# 04-Accel.net
KiCad netlist of a schematic drawn in Altium Designer
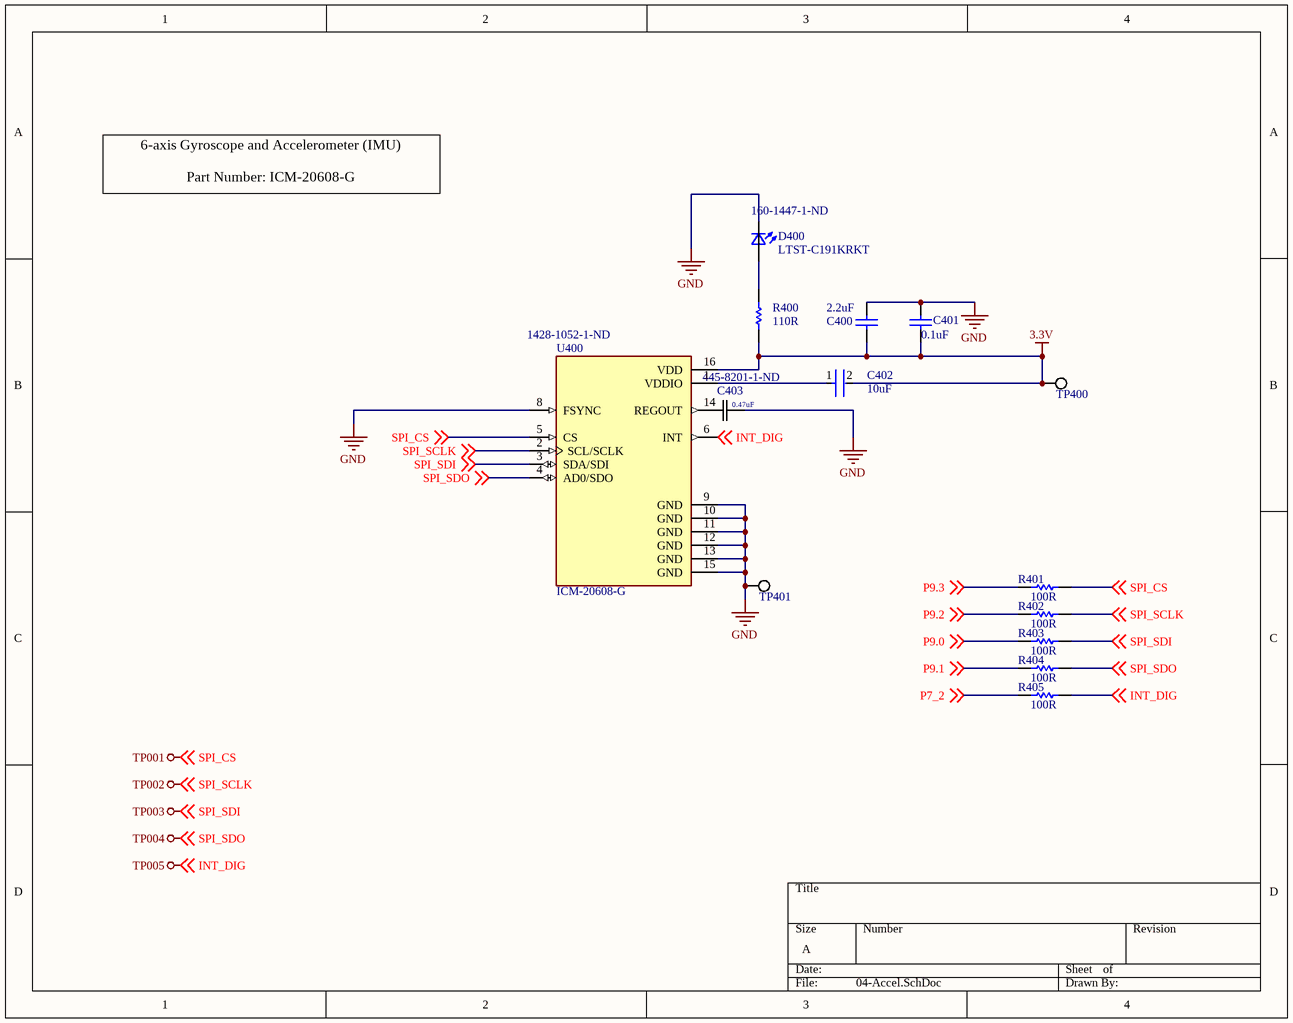
[diagram p0: 04-Accel.SchDoc]

(export (version "E")
  (design (tool "Eeschema 10.0.6"))
  (components
    (comp (ref "C400")
      (value "2.2uF")
      (footprint "CAPC2013X145X50ML20T25")
      (fields (field (name "PART NUMBER") "C0805C225K9PACTU") (field (name "MANUFACTURER") "Kemet"))
      (libsource (lib "Altium Content Vault") (part "CAP"))
    )
    (comp (ref "C401")
      (value "0.1uF")
      (footprint "CAPC2013X145X50LL20T25")
      (fields (field (name "MANUFACTURER") "Kemet") (field (name "PART NUMBER") "C0805C104K9RACTU"))
      (libsource (lib "Altium Content Vault") (part "CAP"))
    )
    (comp (ref "C402")
      (value "10uF")
      (footprint "FP-C0805C-DN-MFG")
      (description "CAP CER 10000PF 10V X7R 0805")
      (fields
        (field (name "MANUFACTURER PART NUMBER") "C0805C103K8RACTU")
        (field (name "OCTOPART") "https://octopart.com/c0805c103k8ractu-kemet-12595572")
      )
      (libsource (lib "Altium Content Vault") (part "b4654b650e69147ec39a6b967a45e02"))
    )
    (comp (ref "C403")
      (value "0.47uF")
      (footprint "CAP_2012_TDK")
      (description "Cap Ceramic 0.47uF 6.3V X7R 10% Pad SMD 0805 125C Automotive T/R")
      (fields
        (field (name "SUPPLIER PART NUMBER 2") "445-8201-1-ND")
        (field (name "MANUFACTURER") "TDK")
        (field (name "MANUFACTURER PART NUMBER") "CGJ4J2X7R0J474K125AA")
      )
      (libsource (lib "CGJ4J2X7R0J474K125AA") (part "CGJ4J2X7R0J474K125AA"))
    )
    (comp (ref "D400")
      (value "LTST-C191KRKT")
      (footprint "0603:0603")
      (description "LED Uni-Color Red 639nm 2-Pin Chip LED T/R / LED RED CLEAR 0603 SMD")
      (fields
        (field (name "SUPPLIER PART NUMBER 1") "160-1447-1-ND")
        (field (name "MANUFACTURER") "Vishay Lite-On")
        (field (name "VOLTAGE") "2V")
      )
      (libsource (lib "LTST-C191KRKT") (part "LTST-C191KRKT"))
    )
    (comp (ref "R400")
      (value "110R")
      (footprint "RESC2013X60X40NL20T25")
      (fields (field (name "PART NUMBER") "ERA6AEB111V") (field (name "MANUFACTURER") "Panasonic"))
      (libsource (lib "Altium Content Vault") (part "RES"))
    )
    (comp (ref "R401")
      (value "100R")
      (footprint "RESC2013X60X40ML20T25")
      (fields (field (name "MANUFACTURER") "Panasonic") (field (name "PART NUMBER") "ERA6AEB101V"))
      (libsource (lib "Altium Content Vault") (part "RES"))
    )
    (comp (ref "R402")
      (value "100R")
      (footprint "RESC2013X60X40ML20T25")
      (fields (field (name "MANUFACTURER") "Panasonic") (field (name "PART NUMBER") "ERA6AEB101V"))
      (libsource (lib "Altium Content Vault") (part "RES"))
    )
    (comp (ref "R403")
      (value "100R")
      (footprint "RESC2013X60X40ML20T25")
      (fields (field (name "MANUFACTURER") "Panasonic") (field (name "PART NUMBER") "ERA6AEB101V"))
      (libsource (lib "Altium Content Vault") (part "RES"))
    )
    (comp (ref "R404")
      (value "100R")
      (footprint "RESC2013X60X40ML20T25")
      (fields (field (name "MANUFACTURER") "Panasonic") (field (name "PART NUMBER") "ERA6AEB101V"))
      (libsource (lib "Altium Content Vault") (part "RES"))
    )
    (comp (ref "R405")
      (value "100R")
      (footprint "RESC2013X60X40ML20T25")
      (fields (field (name "MANUFACTURER") "Panasonic") (field (name "PART NUMBER") "ERA6AEB101V"))
      (libsource (lib "Altium Content Vault") (part "RES"))
    )
    (comp (ref "TP400")
      (value "5019")
      (footprint "KSTN-5019_V")
      (description "Test Point, 1 Position SMD, RoHS, Tape and Reel")
      (libsource (lib "Altium Content Vault") (part "TESTPOINT_WHITE"))
    )
    (comp (ref "TP401")
      (value "5019")
      (footprint "KSTN-5019_V")
      (description "Test Point, 1 Position SMD, RoHS, Tape and Reel")
      (libsource (lib "Altium Content Vault") (part "TESTPOINT_WHITE"))
    )
    (comp (ref "U400")
      (value "ICM-20608-G")
      (footprint "PQFN50P300X300X80-16N")
      (description "MotionTracking Device Digital Output 1.8V 16-Pin LGA / IMU ACCEL/GYRO I2C/SPI 16LGA")
      (fields (field (name "MF") "TDK InvenSense") (field (name "SUPPLIER PART NUMBER 1") "1428-1052-1-ND"))
      (libsource (lib "ICM-20608-G") (part "ICM-20608-G"))
    )
  )
  (nets
    (net (code "1") (name "3.3V") (class "Default")
      (node (ref "C400") (pin "1") (pinfunction "1_1") (pintype "passive"))
      (node (ref "C401") (pin "1") (pinfunction "1_1") (pintype "passive"))
      (node (ref "C402") (pin "2") (pinfunction "2_2") (pintype "passive"))
      (node (ref "R400") (pin "1") (pinfunction "1_1") (pintype "passive"))
      (node (ref "TP400") (pin "1") (pinfunction "1_1") (pintype "passive"))
      (node (ref "U400") (pin "16") (pinfunction "VDD_16") (pintype "power_in"))
    )
    (net (code "2") (name "GND") (class "Default")
      (node (ref "C400") (pin "2") (pinfunction "2_2") (pintype "passive"))
      (node (ref "C401") (pin "2") (pinfunction "2_2") (pintype "passive"))
      (node (ref "C403") (pin "2") (pinfunction "2_2") (pintype "passive"))
      (node (ref "D400") (pin "1") (pinfunction "K2_1") (pintype "passive"))
      (node (ref "TP401") (pin "1") (pinfunction "1_1") (pintype "passive"))
      (node (ref "U400") (pin "10") (pinfunction "GND_10") (pintype "power_in"))
      (node (ref "U400") (pin "11") (pinfunction "GND_11") (pintype "power_in"))
      (node (ref "U400") (pin "12") (pinfunction "GND_12") (pintype "power_in"))
      (node (ref "U400") (pin "13") (pinfunction "GND_13") (pintype "power_in"))
      (node (ref "U400") (pin "15") (pinfunction "GND_15") (pintype "power_in"))
      (node (ref "U400") (pin "8") (pinfunction "FSYNC_8") (pintype "input"))
      (node (ref "U400") (pin "9") (pinfunction "GND_9") (pintype "power_in"))
    )
    (net (code "3") (name "INT_DIG") (class "Default")
      (node (ref "R405") (pin "2") (pinfunction "2_2") (pintype "passive"))
      (node (ref "U400") (pin "6") (pinfunction "INT_6") (pintype "output"))
    )
    (net (code "4") (name "Net-(D400-A2)") (class "Default")
      (node (ref "D400") (pin "2") (pinfunction "A2_2") (pintype "passive"))
      (node (ref "R400") (pin "2") (pinfunction "2_2") (pintype "passive"))
    )
    (net (code "5") (name "Net-(U400-VDDIO)") (class "Default")
      (node (ref "C402") (pin "1") (pinfunction "1_1") (pintype "passive"))
      (node (ref "U400") (pin "1") (pinfunction "VDDIO_1") (pintype "power_in"))
    )
    (net (code "6") (name "P7_2") (class "Default")
      (node (ref "R405") (pin "1") (pinfunction "1_1") (pintype "passive"))
    )
    (net (code "7") (name "P9.0") (class "Default")
      (node (ref "R403") (pin "1") (pinfunction "1_1") (pintype "passive"))
    )
    (net (code "8") (name "P9.1") (class "Default")
      (node (ref "R404") (pin "1") (pinfunction "1_1") (pintype "passive"))
    )
    (net (code "9") (name "P9.2") (class "Default")
      (node (ref "R402") (pin "1") (pinfunction "1_1") (pintype "passive"))
    )
    (net (code "10") (name "P9.3") (class "Default")
      (node (ref "R401") (pin "1") (pinfunction "1_1") (pintype "passive"))
    )
    (net (code "11") (name "SPI_CS") (class "Default")
      (node (ref "R401") (pin "2") (pinfunction "2_2") (pintype "passive"))
      (node (ref "U400") (pin "5") (pinfunction "CS_5") (pintype "input"))
    )
    (net (code "12") (name "SPI_SCLK") (class "Default")
      (node (ref "R402") (pin "2") (pinfunction "2_2") (pintype "passive"))
      (node (ref "U400") (pin "2") (pinfunction "SCL/SCLK_2") (pintype "input"))
    )
    (net (code "13") (name "SPI_SDI") (class "Default")
      (node (ref "R403") (pin "2") (pinfunction "2_2") (pintype "passive"))
      (node (ref "U400") (pin "3") (pinfunction "SDA/SDI_3") (pintype "bidirectional"))
    )
    (net (code "14") (name "SPI_SDO") (class "Default")
      (node (ref "R404") (pin "2") (pinfunction "2_2") (pintype "passive"))
      (node (ref "U400") (pin "4") (pinfunction "AD0/SDO_4") (pintype "bidirectional"))
    )
    (net (code "15") (name "unconnected-(C403-Pad1)") (class "Default")
      (node (ref "C403") (pin "1") (pinfunction "1_1") (pintype "passive"))
    )
    (net (code "16") (name "unconnected-(U400-REGOUT-Pad14)") (class "Default")
      (node (ref "U400") (pin "14") (pinfunction "REGOUT_14") (pintype "output"))
    )
  )
)
